# powerStageC_rev3.net
KiCad netlist of a schematic drawn in EAGLE
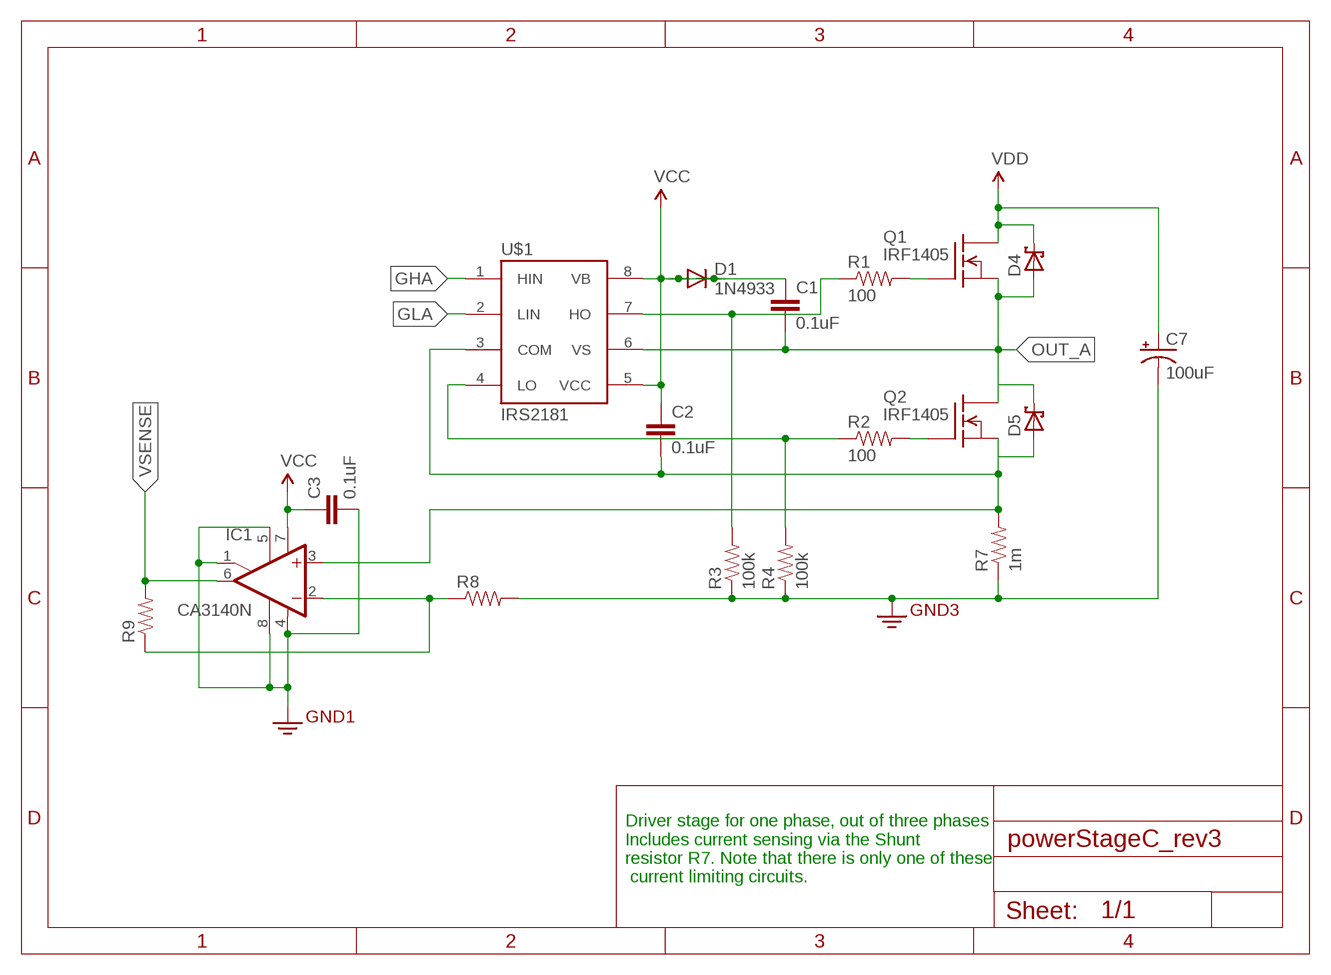
[diagram p0: schematic, sheet 1]

(export (version "E")
  (design (tool "Eeschema 10.0.6"))
  (components
    (comp (ref "C1")
      (value "0.1uF")
      (footprint "eagle-import:0603-CAP")
      (libsource (lib "eagle-import") (part "0.1UF-25V(+80/-20%)(0603)"))
    )
    (comp (ref "C2")
      (value "0.1uF")
      (footprint "eagle-import:0603-CAP")
      (libsource (lib "eagle-import") (part "0.1UF-25V(+80/-20%)(0603)"))
    )
    (comp (ref "C3")
      (value "0.1uF")
      (footprint "eagle-import:0603-CAP")
      (libsource (lib "eagle-import") (part "0.1UF-25V(+80/-20%)(0603)"))
    )
    (comp (ref "C7")
      (value "100uF")
      (footprint "eagle-import:PANASONIC_H13")
      (libsource (lib "eagle-import") (part "100UF-63V-20%(ELECT)"))
    )
    (comp (ref "D1")
      (value "1N4933")
      (footprint "eagle-import:DO41-10")
      (libsource (lib "eagle-import") (part "1N4933"))
    )
    (comp (ref "D4")
      (value "SCHOTTKY-DIODEDO41")
      (footprint "eagle-import:DO41-10")
      (libsource (lib "eagle-import") (part "SCHOTTKY-DIODEDO41"))
    )
    (comp (ref "D5")
      (value "SCHOTTKY-DIODEDO41")
      (footprint "eagle-import:DO41-10")
      (libsource (lib "eagle-import") (part "SCHOTTKY-DIODEDO41"))
    )
    (comp (ref "IC1")
      (value "CA3140N")
      (footprint "eagle-import:DIL08")
      (libsource (lib "eagle-import") (part "CA3140N"))
    )
    (comp (ref "Q1")
      (value "IRF1405")
      (footprint "eagle-import:TO220")
      (libsource (lib "eagle-import") (part "IRF540"))
    )
    (comp (ref "Q2")
      (value "IRF1405")
      (footprint "eagle-import:TO220")
      (libsource (lib "eagle-import") (part "IRF540"))
    )
    (comp (ref "R1")
      (value "100")
      (footprint "eagle-import:AXIAL-0.3")
      (libsource (lib "eagle-import") (part "SparkFun-Resistors_RESISTORAXIAL-0.3"))
    )
    (comp (ref "R2")
      (value "100")
      (footprint "eagle-import:AXIAL-0.3")
      (libsource (lib "eagle-import") (part "SparkFun-Resistors_RESISTORAXIAL-0.3"))
    )
    (comp (ref "R3")
      (value "100k")
      (footprint "eagle-import:AXIAL-0.3")
      (libsource (lib "eagle-import") (part "SparkFun-Resistors_RESISTORAXIAL-0.3"))
    )
    (comp (ref "R4")
      (value "100k")
      (footprint "eagle-import:AXIAL-0.3")
      (libsource (lib "eagle-import") (part "SparkFun-Resistors_RESISTORAXIAL-0.3"))
    )
    (comp (ref "R7")
      (value "1m")
      (footprint "eagle-import:AXIAL-0.8")
      (libsource (lib "eagle-import") (part "RESISTORPTH-2W"))
    )
    (comp (ref "R8")
      (value "RESISTORAXIAL-0.3")
      (footprint "eagle-import:AXIAL-0.3")
      (libsource (lib "eagle-import") (part "SparkFun-Resistors_RESISTORAXIAL-0.3"))
    )
    (comp (ref "R9")
      (value "RESISTORAXIAL-0.3")
      (footprint "eagle-import:AXIAL-0.3")
      (libsource (lib "eagle-import") (part "SparkFun-Resistors_RESISTORAXIAL-0.3"))
    )
    (comp (ref "U$1")
      (value "IRS2181")
      (footprint "eagle-import:DIP08")
      (libsource (lib "eagle-import") (part "IRS2181"))
    )
  )
  (nets
    (net (code "1") (name "GHA") (class "Default")
      (node (ref "U$1") (pin "1") (pinfunction "HIN_1") (pintype "bidirectional"))
    )
    (net (code "2") (name "GLA") (class "Default")
      (node (ref "U$1") (pin "2") (pinfunction "LIN_2") (pintype "bidirectional"))
    )
    (net (code "3") (name "GND2") (class "Default")
      (node (ref "C3") (pin "2") (pinfunction "2_2") (pintype "passive"))
      (node (ref "C7") (pin "-") (pinfunction "-_-") (pintype "passive"))
      (node (ref "IC1") (pin "1") (pinfunction "ON/CMP_1") (pintype "passive"))
      (node (ref "IC1") (pin "4") (pinfunction "V-_4") (pintype "power_in"))
      (node (ref "IC1") (pin "5") (pinfunction "ON_5") (pintype "passive"))
      (node (ref "IC1") (pin "8") (pinfunction "CMP_8") (pintype "passive"))
      (node (ref "R3") (pin "P$1") (pinfunction "1_P$1") (pintype "passive"))
      (node (ref "R4") (pin "P$1") (pinfunction "1_P$1") (pintype "passive"))
      (node (ref "R7") (pin "P$1") (pinfunction "1_P$1") (pintype "passive"))
      (node (ref "R8") (pin "P$2") (pinfunction "2_P$2") (pintype "passive"))
    )
    (net (code "4") (name "Net-(IC1-+IN)") (class "Default")
      (node (ref "C2") (pin "2") (pinfunction "2_2") (pintype "passive"))
      (node (ref "IC1") (pin "3") (pinfunction "+IN_3") (pintype "input"))
      (node (ref "Q2") (pin "3") (pinfunction "S_3") (pintype "passive"))
      (node (ref "R7") (pin "P$2") (pinfunction "2_P$2") (pintype "passive"))
      (node (ref "U$1") (pin "3") (pinfunction "COM_3") (pintype "bidirectional"))
    )
    (net (code "5") (name "Net-(IC1--IN)") (class "Default")
      (node (ref "IC1") (pin "2") (pinfunction "-IN_2") (pintype "input"))
      (node (ref "R8") (pin "P$1") (pinfunction "1_P$1") (pintype "passive"))
      (node (ref "R9") (pin "P$1") (pinfunction "1_P$1") (pintype "passive"))
    )
    (net (code "6") (name "Net-(Q1-G)") (class "Default")
      (node (ref "Q1") (pin "1") (pinfunction "G_1") (pintype "passive"))
      (node (ref "R1") (pin "P$2") (pinfunction "2_P$2") (pintype "passive"))
    )
    (net (code "7") (name "Net-(Q2-G)") (class "Default")
      (node (ref "Q2") (pin "1") (pinfunction "G_1") (pintype "passive"))
      (node (ref "R2") (pin "P$2") (pinfunction "2_P$2") (pintype "passive"))
    )
    (net (code "8") (name "Net-(R1-1)") (class "Default")
      (node (ref "R1") (pin "P$1") (pinfunction "1_P$1") (pintype "passive"))
      (node (ref "R3") (pin "P$2") (pinfunction "2_P$2") (pintype "passive"))
      (node (ref "U$1") (pin "7") (pinfunction "HO_7") (pintype "bidirectional"))
    )
    (net (code "9") (name "Net-(R2-1)") (class "Default")
      (node (ref "R2") (pin "P$1") (pinfunction "1_P$1") (pintype "passive"))
      (node (ref "R4") (pin "P$2") (pinfunction "2_P$2") (pintype "passive"))
      (node (ref "U$1") (pin "4") (pinfunction "LO_4") (pintype "bidirectional"))
    )
    (net (code "10") (name "OUT_A") (class "Default")
      (node (ref "C1") (pin "2") (pinfunction "2_2") (pintype "passive"))
      (node (ref "D4") (pin "A") (pinfunction "A_A") (pintype "passive"))
      (node (ref "Q1") (pin "3") (pinfunction "S_3") (pintype "passive"))
      (node (ref "Q2") (pin "2") (pinfunction "D_2") (pintype "passive"))
      (node (ref "U$1") (pin "6") (pinfunction "VS_6") (pintype "bidirectional"))
    )
    (net (code "11") (name "VCC") (class "Default")
      (node (ref "C1") (pin "1") (pinfunction "1_1") (pintype "passive"))
      (node (ref "C2") (pin "1") (pinfunction "1_1") (pintype "passive"))
      (node (ref "C3") (pin "1") (pinfunction "1_1") (pintype "passive"))
      (node (ref "D1") (pin "A") (pinfunction "A_A") (pintype "passive"))
      (node (ref "D1") (pin "C") (pinfunction "C_C") (pintype "passive"))
      (node (ref "IC1") (pin "7") (pinfunction "V+_7") (pintype "power_in"))
      (node (ref "U$1") (pin "5") (pinfunction "VCC_5") (pintype "bidirectional"))
      (node (ref "U$1") (pin "8") (pinfunction "VB_8") (pintype "bidirectional"))
    )
    (net (code "12") (name "VDD") (class "Default")
      (node (ref "C7") (pin "+") (pinfunction "+_+") (pintype "passive"))
      (node (ref "D4") (pin "C") (pinfunction "C_C") (pintype "passive"))
      (node (ref "Q1") (pin "2") (pinfunction "D_2") (pintype "passive"))
    )
    (net (code "13") (name "VSENSE") (class "Default")
      (node (ref "IC1") (pin "6") (pinfunction "OUT_6") (pintype "output"))
      (node (ref "R9") (pin "P$2") (pinfunction "2_P$2") (pintype "passive"))
    )
    (net (code "14") (name "unconnected-(D5-PadA)") (class "Default")
      (node (ref "D5") (pin "A") (pinfunction "A_A") (pintype "passive"))
    )
    (net (code "15") (name "unconnected-(D5-PadC)") (class "Default")
      (node (ref "D5") (pin "C") (pinfunction "C_C") (pintype "passive"))
    )
  )
)
